# Teseo.net
KiCad netlist of a schematic drawn in EAGLE
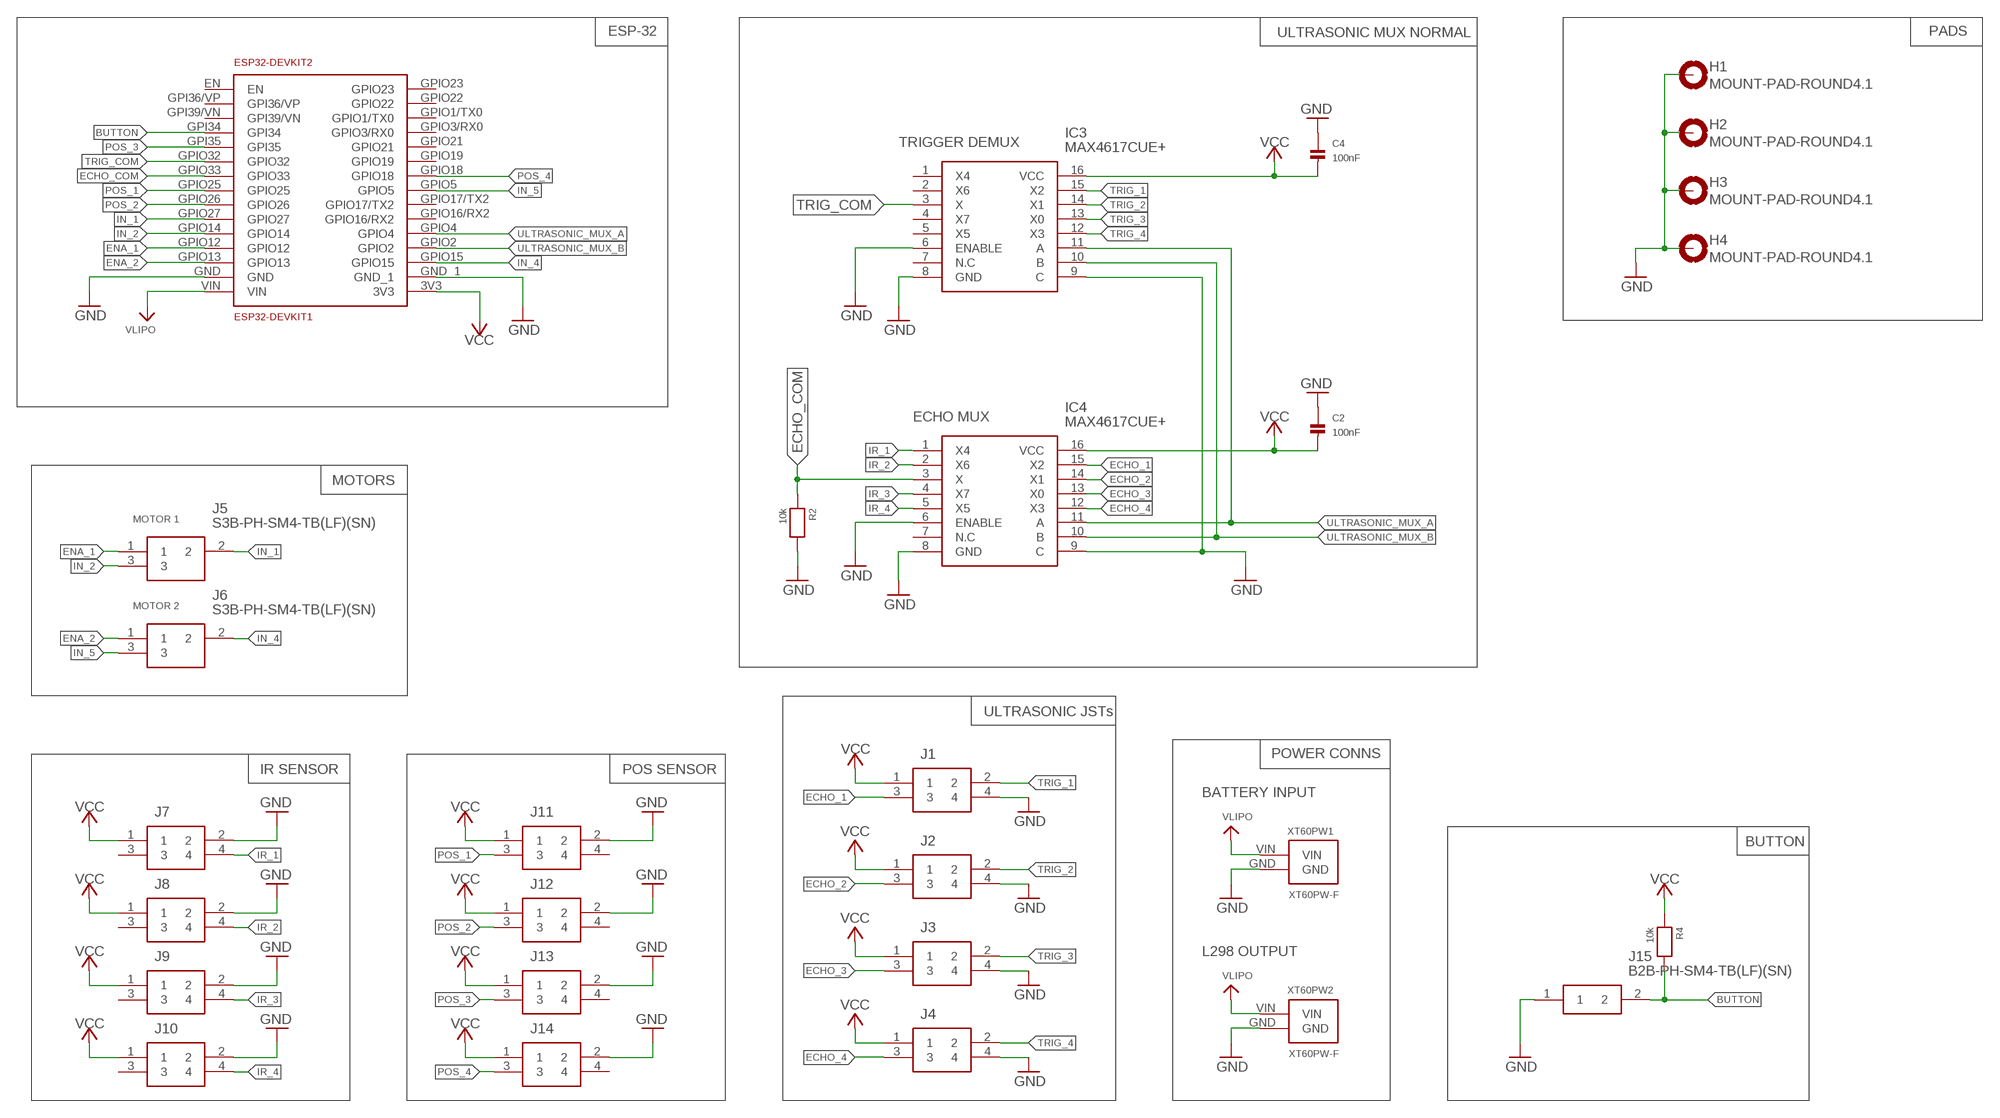
[diagram p0: schematic, sheet 1]

(export (version "E")
  (design (tool "Eeschema 10.0.6"))
  (components
    (comp (ref "C2")
      (value "100nF")
      (footprint "eagle-import:0805")
      (libsource (lib "eagle-import") (part "CAP_CERAMIC0805"))
    )
    (comp (ref "C4")
      (value "100nF")
      (footprint "eagle-import:0805")
      (libsource (lib "eagle-import") (part "CAP_CERAMIC0805"))
    )
    (comp (ref "ESP32-DEVKIT2")
      (value "ESP32-DEVKIT1")
      (footprint "eagle-import:ESP32-DEVKIT1")
      (libsource (lib "eagle-import") (part "ESP32-DEVKIT1"))
    )
    (comp (ref "H1")
      (value "MOUNT-PAD-ROUND4.1")
      (footprint "eagle-import:4,1-PAD")
      (libsource (lib "eagle-import") (part "MOUNT-PAD-ROUND4.1"))
    )
    (comp (ref "H2")
      (value "MOUNT-PAD-ROUND4.1")
      (footprint "eagle-import:4,1-PAD")
      (libsource (lib "eagle-import") (part "MOUNT-PAD-ROUND4.1"))
    )
    (comp (ref "H3")
      (value "MOUNT-PAD-ROUND4.1")
      (footprint "eagle-import:4,1-PAD")
      (libsource (lib "eagle-import") (part "MOUNT-PAD-ROUND4.1"))
    )
    (comp (ref "H4")
      (value "MOUNT-PAD-ROUND4.1")
      (footprint "eagle-import:4,1-PAD")
      (libsource (lib "eagle-import") (part "MOUNT-PAD-ROUND4.1"))
    )
    (comp (ref "IC3")
      (value "MAX4617CUE+")
      (footprint "eagle-import:SOP65P640X110-16N")
      (fields (field (name "MOUSER_PART_NUMBER") "700-MAX4617CUE"))
      (libsource (lib "eagle-import") (part "MAX4617CUE+"))
    )
    (comp (ref "IC4")
      (value "MAX4617CUE+")
      (footprint "eagle-import:SOP65P640X110-16N")
      (fields (field (name "MOUSER_PART_NUMBER") "700-MAX4617CUE"))
      (libsource (lib "eagle-import") (part "MAX4617CUE+"))
    )
    (comp (ref "J1")
      (value "S4B-PH-SM4-TB(LF)(SN)")
      (footprint "eagle-import:S4B-PH-SM4-TB")
      (fields (field (name "RS_PART_NUMBER") "6881366P"))
      (libsource (lib "eagle-import") (part "S4B-PH-SM4-TB(LF)(SN)"))
    )
    (comp (ref "J2")
      (value "S4B-PH-SM4-TB(LF)(SN)")
      (footprint "eagle-import:S4B-PH-SM4-TB")
      (fields (field (name "RS_PART_NUMBER") "6881366P"))
      (libsource (lib "eagle-import") (part "S4B-PH-SM4-TB(LF)(SN)"))
    )
    (comp (ref "J3")
      (value "S4B-PH-SM4-TB(LF)(SN)")
      (footprint "eagle-import:S4B-PH-SM4-TB")
      (fields (field (name "RS_PART_NUMBER") "6881366P"))
      (libsource (lib "eagle-import") (part "S4B-PH-SM4-TB(LF)(SN)"))
    )
    (comp (ref "J4")
      (value "S4B-PH-SM4-TB(LF)(SN)")
      (footprint "eagle-import:S4B-PH-SM4-TB")
      (fields (field (name "RS_PART_NUMBER") "6881366P"))
      (libsource (lib "eagle-import") (part "S4B-PH-SM4-TB(LF)(SN)"))
    )
    (comp (ref "J5")
      (value "S3B-PH-SM4-TB(LF)(SN)")
      (footprint "eagle-import:S3B-PH-SM4-TB")
      (fields (field (name "RS_PART_NUMBER") "6881357P"))
      (libsource (lib "eagle-import") (part "S3B-PH-SM4-TB(LF)(SN)"))
    )
    (comp (ref "J6")
      (value "S3B-PH-SM4-TB(LF)(SN)")
      (footprint "eagle-import:S3B-PH-SM4-TB")
      (fields (field (name "RS_PART_NUMBER") "6881357P"))
      (libsource (lib "eagle-import") (part "S3B-PH-SM4-TB(LF)(SN)"))
    )
    (comp (ref "J7")
      (value "S4B-PH-SM4-TB(LF)(SN)")
      (footprint "eagle-import:S4B-PH-SM4-TB")
      (fields (field (name "RS_PART_NUMBER") "6881366P"))
      (libsource (lib "eagle-import") (part "S4B-PH-SM4-TB(LF)(SN)"))
    )
    (comp (ref "J8")
      (value "S4B-PH-SM4-TB(LF)(SN)")
      (footprint "eagle-import:S4B-PH-SM4-TB")
      (fields (field (name "RS_PART_NUMBER") "6881366P"))
      (libsource (lib "eagle-import") (part "S4B-PH-SM4-TB(LF)(SN)"))
    )
    (comp (ref "J9")
      (value "S4B-PH-SM4-TB(LF)(SN)")
      (footprint "eagle-import:S4B-PH-SM4-TB")
      (fields (field (name "RS_PART_NUMBER") "6881366P"))
      (libsource (lib "eagle-import") (part "S4B-PH-SM4-TB(LF)(SN)"))
    )
    (comp (ref "J10")
      (value "S4B-PH-SM4-TB(LF)(SN)")
      (footprint "eagle-import:S4B-PH-SM4-TB")
      (fields (field (name "RS_PART_NUMBER") "6881366P"))
      (libsource (lib "eagle-import") (part "S4B-PH-SM4-TB(LF)(SN)"))
    )
    (comp (ref "J11")
      (value "S4B-PH-SM4-TB(LF)(SN)")
      (footprint "eagle-import:S4B-PH-SM4-TB")
      (fields (field (name "RS_PART_NUMBER") "6881366P"))
      (libsource (lib "eagle-import") (part "S4B-PH-SM4-TB(LF)(SN)"))
    )
    (comp (ref "J12")
      (value "S4B-PH-SM4-TB(LF)(SN)")
      (footprint "eagle-import:S4B-PH-SM4-TB")
      (fields (field (name "RS_PART_NUMBER") "6881366P"))
      (libsource (lib "eagle-import") (part "S4B-PH-SM4-TB(LF)(SN)"))
    )
    (comp (ref "J13")
      (value "S4B-PH-SM4-TB(LF)(SN)")
      (footprint "eagle-import:S4B-PH-SM4-TB")
      (fields (field (name "RS_PART_NUMBER") "6881366P"))
      (libsource (lib "eagle-import") (part "S4B-PH-SM4-TB(LF)(SN)"))
    )
    (comp (ref "J14")
      (value "S4B-PH-SM4-TB(LF)(SN)")
      (footprint "eagle-import:S4B-PH-SM4-TB")
      (fields (field (name "RS_PART_NUMBER") "6881366P"))
      (libsource (lib "eagle-import") (part "S4B-PH-SM4-TB(LF)(SN)"))
    )
    (comp (ref "J15")
      (value "B2B-PH-SM4-TB(LF)(SN)")
      (footprint "eagle-import:B2B-PH-SM4-TB")
      (fields (field (name "RS_PART_NUMBER") "6881325P"))
      (libsource (lib "eagle-import") (part "B2B-PH-SM4-TB(LF)(SN)"))
    )
    (comp (ref "R2")
      (value "10k")
      (footprint "eagle-import:_0805")
      (libsource (lib "eagle-import") (part "RESISTOR_0805"))
    )
    (comp (ref "R4")
      (value "10k")
      (footprint "eagle-import:_0805")
      (libsource (lib "eagle-import") (part "RESISTOR_0805"))
    )
    (comp (ref "XT60PW1")
      (value "XT60PW-F")
      (footprint "eagle-import:XT60PW-F")
      (fields (field (name "SPICEPREFIX") "X"))
      (libsource (lib "eagle-import") (part "XT60PW-F"))
    )
    (comp (ref "XT60PW2")
      (value "XT60PW-F")
      (footprint "eagle-import:XT60PW-F")
      (fields (field (name "SPICEPREFIX") "X"))
      (libsource (lib "eagle-import") (part "XT60PW-F"))
    )
  )
  (nets
    (net (code "1") (name "BUTTON") (class "Default")
      (node (ref "ESP32-DEVKIT2") (pin "GPI34") (pinfunction "GPI34_GPI34") (pintype "bidirectional"))
      (node (ref "J15") (pin "2") (pinfunction "2_2") (pintype "bidirectional"))
      (node (ref "R4") (pin "2") (pinfunction "2_2") (pintype "passive"))
    )
    (net (code "2") (name "ECHO_1") (class "Default")
      (node (ref "IC4") (pin "15") (pinfunction "X2_15") (pintype "output"))
      (node (ref "J1") (pin "3") (pinfunction "3_3") (pintype "bidirectional"))
    )
    (net (code "3") (name "ECHO_2") (class "Default")
      (node (ref "IC4") (pin "14") (pinfunction "X1_14") (pintype "output"))
      (node (ref "J2") (pin "3") (pinfunction "3_3") (pintype "bidirectional"))
    )
    (net (code "4") (name "ECHO_3") (class "Default")
      (node (ref "IC4") (pin "13") (pinfunction "X0_13") (pintype "output"))
      (node (ref "J3") (pin "3") (pinfunction "3_3") (pintype "bidirectional"))
    )
    (net (code "5") (name "ECHO_4") (class "Default")
      (node (ref "IC4") (pin "12") (pinfunction "X3_12") (pintype "output"))
      (node (ref "J4") (pin "3") (pinfunction "3_3") (pintype "bidirectional"))
    )
    (net (code "6") (name "ECHO_COM") (class "Default")
      (node (ref "ESP32-DEVKIT2") (pin "GPIO33") (pinfunction "GPIO33_GPIO33") (pintype "bidirectional"))
      (node (ref "IC4") (pin "3") (pinfunction "X_3") (pintype "input"))
      (node (ref "R2") (pin "1") (pinfunction "1_1") (pintype "passive"))
    )
    (net (code "7") (name "ENA_1") (class "Default")
      (node (ref "ESP32-DEVKIT2") (pin "GPIO12") (pinfunction "GPIO12_GPIO12") (pintype "bidirectional"))
      (node (ref "J5") (pin "1") (pinfunction "1_1") (pintype "bidirectional"))
    )
    (net (code "8") (name "ENA_2") (class "Default")
      (node (ref "ESP32-DEVKIT2") (pin "GPIO13") (pinfunction "GPIO13_GPIO13") (pintype "bidirectional"))
      (node (ref "J6") (pin "1") (pinfunction "1_1") (pintype "bidirectional"))
    )
    (net (code "9") (name "GND") (class "Default")
      (node (ref "C2") (pin "1") (pinfunction "P$1_1") (pintype "passive"))
      (node (ref "C4") (pin "1") (pinfunction "P$1_1") (pintype "passive"))
      (node (ref "ESP32-DEVKIT2") (pin "GND") (pinfunction "GND_GND") (pintype "bidirectional"))
      (node (ref "ESP32-DEVKIT2") (pin "GND_1") (pinfunction "GND_1_GND_1") (pintype "bidirectional"))
      (node (ref "H1") (pin "B4,1") (pinfunction "MOUNT_B4,1") (pintype "passive"))
      (node (ref "H2") (pin "B4,1") (pinfunction "MOUNT_B4,1") (pintype "passive"))
      (node (ref "H3") (pin "B4,1") (pinfunction "MOUNT_B4,1") (pintype "passive"))
      (node (ref "H4") (pin "B4,1") (pinfunction "MOUNT_B4,1") (pintype "passive"))
      (node (ref "IC3") (pin "6") (pinfunction "ENABLE_6") (pintype "input"))
      (node (ref "IC3") (pin "8") (pinfunction "GND_8") (pintype "power_in"))
      (node (ref "IC3") (pin "9") (pinfunction "C_9") (pintype "input"))
      (node (ref "IC4") (pin "6") (pinfunction "ENABLE_6") (pintype "input"))
      (node (ref "IC4") (pin "8") (pinfunction "GND_8") (pintype "power_in"))
      (node (ref "IC4") (pin "9") (pinfunction "C_9") (pintype "input"))
      (node (ref "J1") (pin "4") (pinfunction "4_4") (pintype "bidirectional"))
      (node (ref "J10") (pin "2") (pinfunction "2_2") (pintype "bidirectional"))
      (node (ref "J11") (pin "2") (pinfunction "2_2") (pintype "bidirectional"))
      (node (ref "J12") (pin "2") (pinfunction "2_2") (pintype "bidirectional"))
      (node (ref "J13") (pin "2") (pinfunction "2_2") (pintype "bidirectional"))
      (node (ref "J14") (pin "2") (pinfunction "2_2") (pintype "bidirectional"))
      (node (ref "J15") (pin "1") (pinfunction "1_1") (pintype "bidirectional"))
      (node (ref "J2") (pin "4") (pinfunction "4_4") (pintype "bidirectional"))
      (node (ref "J3") (pin "4") (pinfunction "4_4") (pintype "bidirectional"))
      (node (ref "J4") (pin "4") (pinfunction "4_4") (pintype "bidirectional"))
      (node (ref "J7") (pin "2") (pinfunction "2_2") (pintype "bidirectional"))
      (node (ref "J8") (pin "2") (pinfunction "2_2") (pintype "bidirectional"))
      (node (ref "J9") (pin "2") (pinfunction "2_2") (pintype "bidirectional"))
      (node (ref "R2") (pin "2") (pinfunction "2_2") (pintype "passive"))
      (node (ref "XT60PW1") (pin "GND") (pinfunction "GND_GND") (pintype "bidirectional"))
      (node (ref "XT60PW2") (pin "GND") (pinfunction "GND_GND") (pintype "bidirectional"))
    )
    (net (code "10") (name "IN_1") (class "Default")
      (node (ref "ESP32-DEVKIT2") (pin "GPIO27") (pinfunction "GPIO27_GPIO27") (pintype "bidirectional"))
      (node (ref "J5") (pin "2") (pinfunction "2_2") (pintype "bidirectional"))
    )
    (net (code "11") (name "IN_2") (class "Default")
      (node (ref "ESP32-DEVKIT2") (pin "GPIO14") (pinfunction "GPIO14_GPIO14") (pintype "bidirectional"))
      (node (ref "J5") (pin "3") (pinfunction "3_3") (pintype "bidirectional"))
    )
    (net (code "12") (name "IN_4") (class "Default")
      (node (ref "ESP32-DEVKIT2") (pin "GPIO15") (pinfunction "GPIO15_GPIO15") (pintype "bidirectional"))
      (node (ref "J6") (pin "2") (pinfunction "2_2") (pintype "bidirectional"))
    )
    (net (code "13") (name "IN_5") (class "Default")
      (node (ref "ESP32-DEVKIT2") (pin "GPIO5") (pinfunction "GPIO5_GPIO5") (pintype "bidirectional"))
      (node (ref "J6") (pin "3") (pinfunction "3_3") (pintype "bidirectional"))
    )
    (net (code "14") (name "IR_1") (class "Default")
      (node (ref "IC4") (pin "1") (pinfunction "X4_1") (pintype "output"))
      (node (ref "J7") (pin "4") (pinfunction "4_4") (pintype "bidirectional"))
    )
    (net (code "15") (name "IR_2") (class "Default")
      (node (ref "IC4") (pin "2") (pinfunction "X6_2") (pintype "output"))
      (node (ref "J8") (pin "4") (pinfunction "4_4") (pintype "bidirectional"))
    )
    (net (code "16") (name "IR_3") (class "Default")
      (node (ref "IC4") (pin "4") (pinfunction "X7_4") (pintype "output"))
      (node (ref "J9") (pin "4") (pinfunction "4_4") (pintype "bidirectional"))
    )
    (net (code "17") (name "IR_4") (class "Default")
      (node (ref "IC4") (pin "5") (pinfunction "X5_5") (pintype "output"))
      (node (ref "J10") (pin "4") (pinfunction "4_4") (pintype "bidirectional"))
    )
    (net (code "18") (name "POS_1") (class "Default")
      (node (ref "ESP32-DEVKIT2") (pin "GPIO25") (pinfunction "GPIO25_GPIO25") (pintype "bidirectional"))
      (node (ref "J11") (pin "3") (pinfunction "3_3") (pintype "bidirectional"))
    )
    (net (code "19") (name "POS_2") (class "Default")
      (node (ref "ESP32-DEVKIT2") (pin "GPIO26") (pinfunction "GPIO26_GPIO26") (pintype "bidirectional"))
      (node (ref "J12") (pin "3") (pinfunction "3_3") (pintype "bidirectional"))
    )
    (net (code "20") (name "POS_3") (class "Default")
      (node (ref "ESP32-DEVKIT2") (pin "GPI35") (pinfunction "GPI35_GPI35") (pintype "bidirectional"))
      (node (ref "J13") (pin "3") (pinfunction "3_3") (pintype "bidirectional"))
    )
    (net (code "21") (name "POS_4") (class "Default")
      (node (ref "ESP32-DEVKIT2") (pin "GPIO18") (pinfunction "GPIO18_GPIO18") (pintype "bidirectional"))
      (node (ref "J14") (pin "3") (pinfunction "3_3") (pintype "bidirectional"))
    )
    (net (code "22") (name "TRIG_1") (class "Default")
      (node (ref "IC3") (pin "15") (pinfunction "X2_15") (pintype "output"))
      (node (ref "J1") (pin "2") (pinfunction "2_2") (pintype "bidirectional"))
    )
    (net (code "23") (name "TRIG_2") (class "Default")
      (node (ref "IC3") (pin "14") (pinfunction "X1_14") (pintype "output"))
      (node (ref "J2") (pin "2") (pinfunction "2_2") (pintype "bidirectional"))
    )
    (net (code "24") (name "TRIG_3") (class "Default")
      (node (ref "IC3") (pin "13") (pinfunction "X0_13") (pintype "output"))
      (node (ref "J3") (pin "2") (pinfunction "2_2") (pintype "bidirectional"))
    )
    (net (code "25") (name "TRIG_4") (class "Default")
      (node (ref "IC3") (pin "12") (pinfunction "X3_12") (pintype "output"))
      (node (ref "J4") (pin "2") (pinfunction "2_2") (pintype "bidirectional"))
    )
    (net (code "26") (name "TRIG_COM") (class "Default")
      (node (ref "ESP32-DEVKIT2") (pin "GPIO32") (pinfunction "GPIO32_GPIO32") (pintype "bidirectional"))
      (node (ref "IC3") (pin "3") (pinfunction "X_3") (pintype "input"))
    )
    (net (code "27") (name "ULTRASONIC_MUX_A") (class "Default")
      (node (ref "ESP32-DEVKIT2") (pin "GPIO4") (pinfunction "GPIO4_GPIO4") (pintype "bidirectional"))
      (node (ref "IC3") (pin "11") (pinfunction "A_11") (pintype "input"))
      (node (ref "IC4") (pin "11") (pinfunction "A_11") (pintype "input"))
    )
    (net (code "28") (name "ULTRASONIC_MUX_B") (class "Default")
      (node (ref "ESP32-DEVKIT2") (pin "GPIO2") (pinfunction "GPIO2_GPIO2") (pintype "bidirectional"))
      (node (ref "IC3") (pin "10") (pinfunction "B_10") (pintype "input"))
      (node (ref "IC4") (pin "10") (pinfunction "B_10") (pintype "input"))
    )
    (net (code "29") (name "VCC") (class "Default")
      (node (ref "C2") (pin "2") (pinfunction "P$2_2") (pintype "passive"))
      (node (ref "C4") (pin "2") (pinfunction "P$2_2") (pintype "passive"))
      (node (ref "ESP32-DEVKIT2") (pin "3V3") (pinfunction "3V3_3V3") (pintype "bidirectional"))
      (node (ref "IC3") (pin "16") (pinfunction "VCC_16") (pintype "power_in"))
      (node (ref "IC4") (pin "16") (pinfunction "VCC_16") (pintype "power_in"))
      (node (ref "J1") (pin "1") (pinfunction "1_1") (pintype "bidirectional"))
      (node (ref "J10") (pin "1") (pinfunction "1_1") (pintype "bidirectional"))
      (node (ref "J11") (pin "1") (pinfunction "1_1") (pintype "bidirectional"))
      (node (ref "J12") (pin "1") (pinfunction "1_1") (pintype "bidirectional"))
      (node (ref "J13") (pin "1") (pinfunction "1_1") (pintype "bidirectional"))
      (node (ref "J14") (pin "1") (pinfunction "1_1") (pintype "bidirectional"))
      (node (ref "J2") (pin "1") (pinfunction "1_1") (pintype "bidirectional"))
      (node (ref "J3") (pin "1") (pinfunction "1_1") (pintype "bidirectional"))
      (node (ref "J4") (pin "1") (pinfunction "1_1") (pintype "bidirectional"))
      (node (ref "J7") (pin "1") (pinfunction "1_1") (pintype "bidirectional"))
      (node (ref "J8") (pin "1") (pinfunction "1_1") (pintype "bidirectional"))
      (node (ref "J9") (pin "1") (pinfunction "1_1") (pintype "bidirectional"))
      (node (ref "R4") (pin "1") (pinfunction "1_1") (pintype "passive"))
    )
    (net (code "30") (name "VLIPO") (class "Default")
      (node (ref "ESP32-DEVKIT2") (pin "VIN") (pinfunction "VIN_VIN") (pintype "bidirectional"))
      (node (ref "XT60PW1") (pin "VIN") (pinfunction "VIN_VIN") (pintype "bidirectional"))
      (node (ref "XT60PW2") (pin "VIN") (pinfunction "VIN_VIN") (pintype "bidirectional"))
    )
    (net (code "31") (name "unconnected-(ESP32-DEVKIT2-PadEN)") (class "Default")
      (node (ref "ESP32-DEVKIT2") (pin "EN") (pinfunction "EN_EN") (pintype "bidirectional"))
    )
    (net (code "32") (name "unconnected-(ESP32-DEVKIT2-PadGPI36{slash}VP)") (class "Default")
      (node (ref "ESP32-DEVKIT2") (pin "GPI36/VP") (pinfunction "GPI36/VP_GPI36/VP") (pintype "bidirectional"))
    )
    (net (code "33") (name "unconnected-(ESP32-DEVKIT2-PadGPI39{slash}VN)") (class "Default")
      (node (ref "ESP32-DEVKIT2") (pin "GPI39/VN") (pinfunction "GPI39/VN_GPI39/VN") (pintype "bidirectional"))
    )
    (net (code "34") (name "unconnected-(ESP32-DEVKIT2-PadGPIO1{slash}TX0)") (class "Default")
      (node (ref "ESP32-DEVKIT2") (pin "GPIO1/TX0") (pinfunction "GPIO1/TX0_GPIO1/TX0") (pintype "bidirectional"))
    )
    (net (code "35") (name "unconnected-(ESP32-DEVKIT2-PadGPIO3{slash}RX0)") (class "Default")
      (node (ref "ESP32-DEVKIT2") (pin "GPIO3/RX0") (pinfunction "GPIO3/RX0_GPIO3/RX0") (pintype "bidirectional"))
    )
    (net (code "36") (name "unconnected-(ESP32-DEVKIT2-PadGPIO16{slash}RX2)") (class "Default")
      (node (ref "ESP32-DEVKIT2") (pin "GPIO16/RX2") (pinfunction "GPIO16/RX2_GPIO16/RX2") (pintype "bidirectional"))
    )
    (net (code "37") (name "unconnected-(ESP32-DEVKIT2-PadGPIO17{slash}TX2)") (class "Default")
      (node (ref "ESP32-DEVKIT2") (pin "GPIO17/TX2") (pinfunction "GPIO17/TX2_GPIO17/TX2") (pintype "bidirectional"))
    )
    (net (code "38") (name "unconnected-(ESP32-DEVKIT2-PadGPIO19)") (class "Default")
      (node (ref "ESP32-DEVKIT2") (pin "GPIO19") (pinfunction "GPIO19_GPIO19") (pintype "bidirectional"))
    )
    (net (code "39") (name "unconnected-(ESP32-DEVKIT2-PadGPIO21)") (class "Default")
      (node (ref "ESP32-DEVKIT2") (pin "GPIO21") (pinfunction "GPIO21_GPIO21") (pintype "bidirectional"))
    )
    (net (code "40") (name "unconnected-(ESP32-DEVKIT2-PadGPIO22)") (class "Default")
      (node (ref "ESP32-DEVKIT2") (pin "GPIO22") (pinfunction "GPIO22_GPIO22") (pintype "bidirectional"))
    )
    (net (code "41") (name "unconnected-(ESP32-DEVKIT2-PadGPIO23)") (class "Default")
      (node (ref "ESP32-DEVKIT2") (pin "GPIO23") (pinfunction "GPIO23_GPIO23") (pintype "bidirectional"))
    )
    (net (code "42") (name "unconnected-(IC3-N.C-Pad7)") (class "Default")
      (node (ref "IC3") (pin "7") (pinfunction "N.C_7") (pintype "no_connect"))
    )
    (net (code "43") (name "unconnected-(IC3-X4-Pad1)") (class "Default")
      (node (ref "IC3") (pin "1") (pinfunction "X4_1") (pintype "output"))
    )
    (net (code "44") (name "unconnected-(IC3-X5-Pad5)") (class "Default")
      (node (ref "IC3") (pin "5") (pinfunction "X5_5") (pintype "output"))
    )
    (net (code "45") (name "unconnected-(IC3-X6-Pad2)") (class "Default")
      (node (ref "IC3") (pin "2") (pinfunction "X6_2") (pintype "output"))
    )
    (net (code "46") (name "unconnected-(IC3-X7-Pad4)") (class "Default")
      (node (ref "IC3") (pin "4") (pinfunction "X7_4") (pintype "output"))
    )
    (net (code "47") (name "unconnected-(IC4-N.C-Pad7)") (class "Default")
      (node (ref "IC4") (pin "7") (pinfunction "N.C_7") (pintype "no_connect"))
    )
    (net (code "48") (name "unconnected-(J7-Pad3)") (class "Default")
      (node (ref "J7") (pin "3") (pinfunction "3_3") (pintype "bidirectional"))
    )
    (net (code "49") (name "unconnected-(J8-Pad3)") (class "Default")
      (node (ref "J8") (pin "3") (pinfunction "3_3") (pintype "bidirectional"))
    )
    (net (code "50") (name "unconnected-(J9-Pad3)") (class "Default")
      (node (ref "J9") (pin "3") (pinfunction "3_3") (pintype "bidirectional"))
    )
    (net (code "51") (name "unconnected-(J10-Pad3)") (class "Default")
      (node (ref "J10") (pin "3") (pinfunction "3_3") (pintype "bidirectional"))
    )
    (net (code "52") (name "unconnected-(J11-Pad4)") (class "Default")
      (node (ref "J11") (pin "4") (pinfunction "4_4") (pintype "bidirectional"))
    )
    (net (code "53") (name "unconnected-(J12-Pad4)") (class "Default")
      (node (ref "J12") (pin "4") (pinfunction "4_4") (pintype "bidirectional"))
    )
    (net (code "54") (name "unconnected-(J13-Pad4)") (class "Default")
      (node (ref "J13") (pin "4") (pinfunction "4_4") (pintype "bidirectional"))
    )
    (net (code "55") (name "unconnected-(J14-Pad4)") (class "Default")
      (node (ref "J14") (pin "4") (pinfunction "4_4") (pintype "bidirectional"))
    )
  )
)
